# main.net
KiCad netlist of a schematic drawn in EAGLE
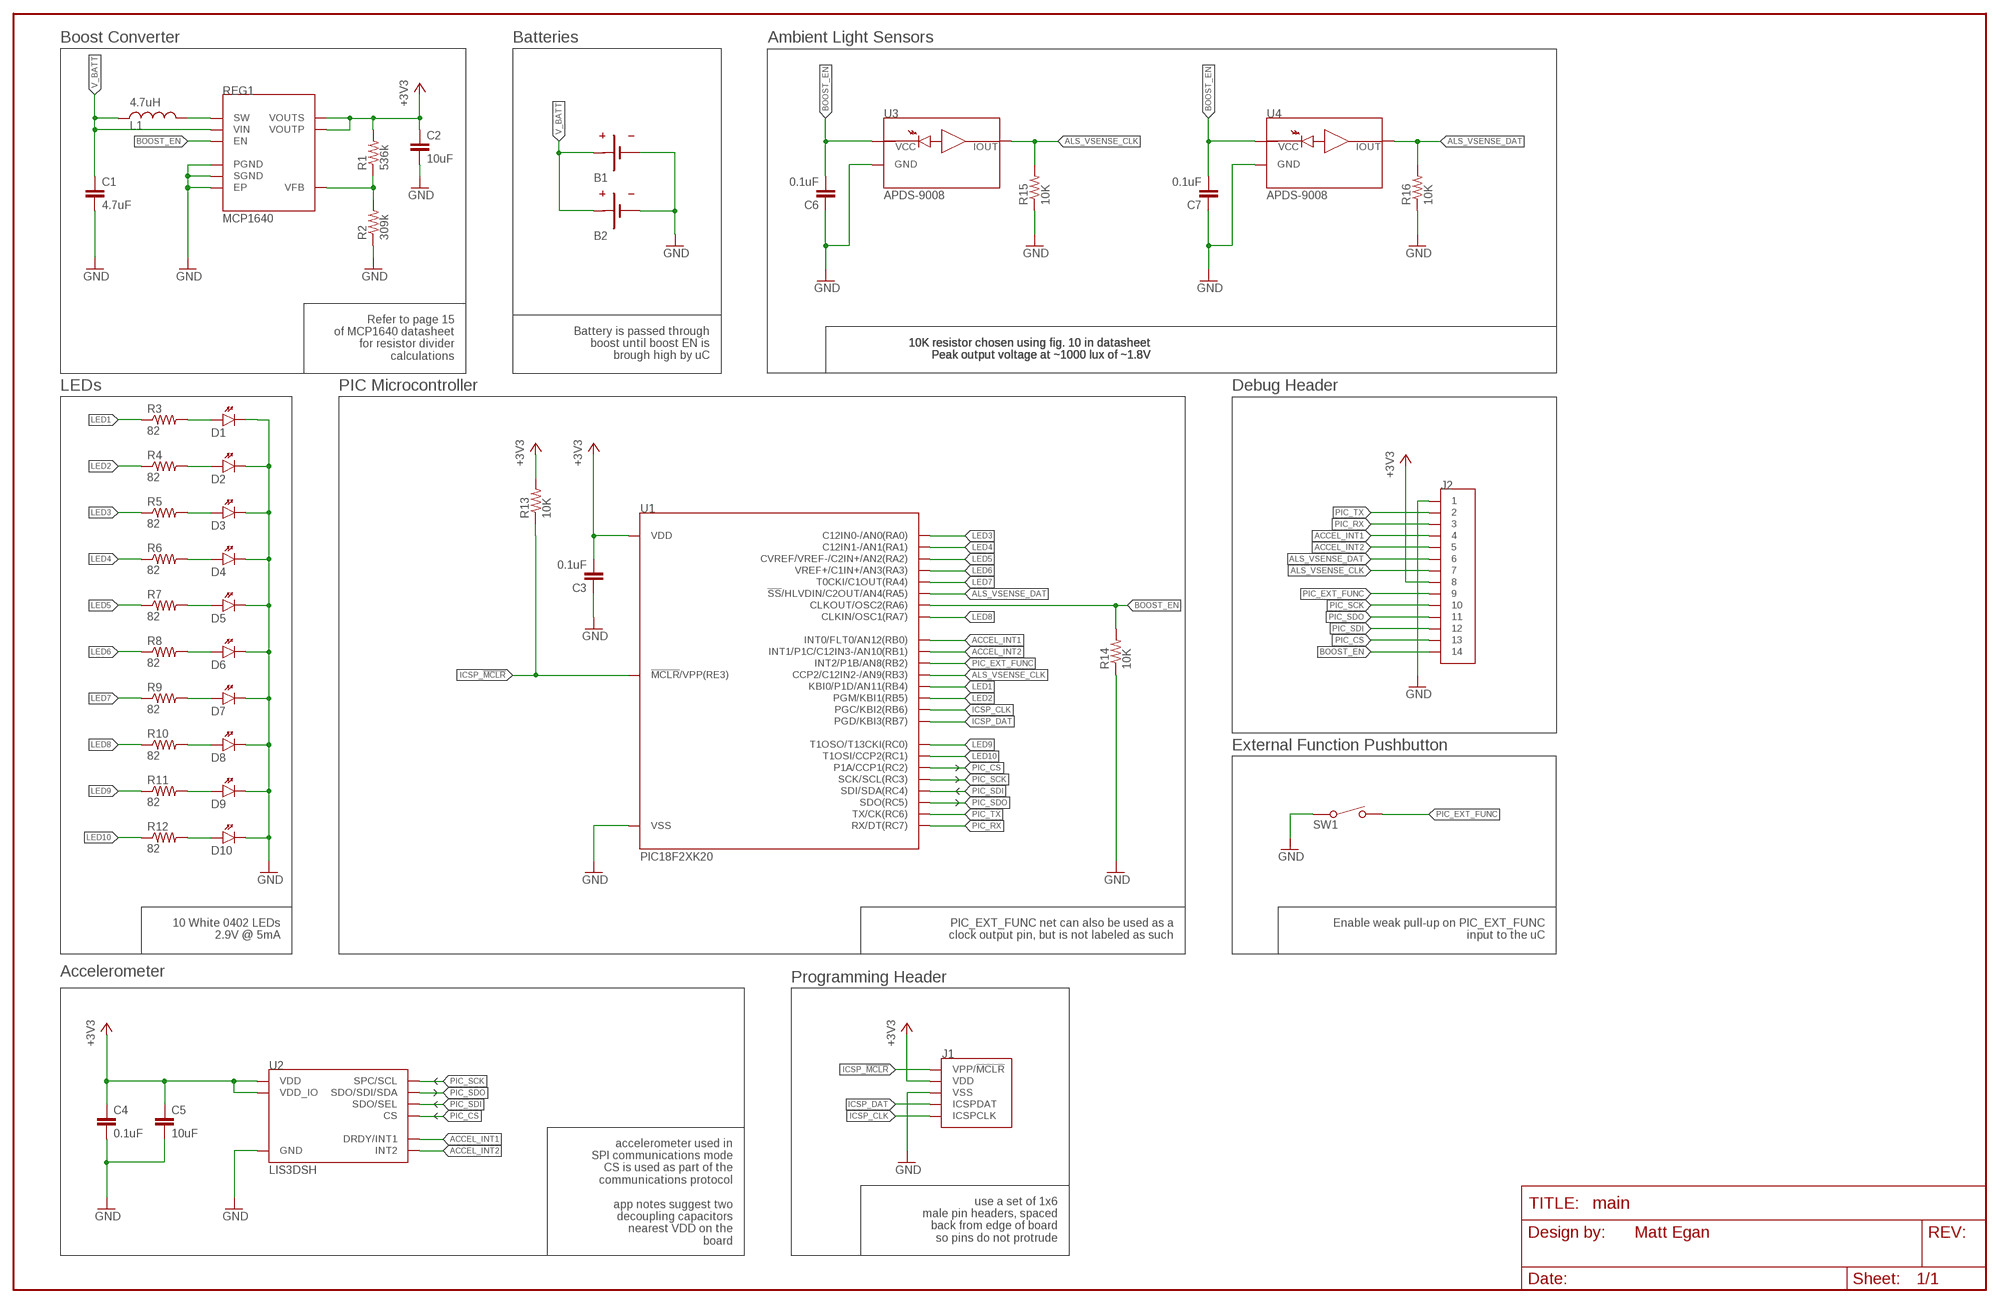
[diagram p0: schematic, sheet 1]

(export (version "E")
  (design (tool "Eeschema 10.0.6"))
  (components
    (comp (ref "B1")
      (value "BATTERYCR-2016/F2N")
      (footprint "eagle-import:CR-2016_F2N")
      (libsource (lib "eagle-import") (part "BATTERYCR-2016/F2N"))
    )
    (comp (ref "B2")
      (value "BATTERYCR-2016/F2N")
      (footprint "eagle-import:CR-2016_F2N")
      (libsource (lib "eagle-import") (part "BATTERYCR-2016/F2N"))
    )
    (comp (ref "C1")
      (value "4.7uF")
      (footprint "eagle-import:SMD-0603")
      (libsource (lib "eagle-import") (part "CAPACITOR0603"))
    )
    (comp (ref "C2")
      (value "10uF")
      (footprint "eagle-import:SMD-0603")
      (libsource (lib "eagle-import") (part "CAPACITOR0603"))
    )
    (comp (ref "C3")
      (value "0.1uF")
      (footprint "eagle-import:SMD-0805")
      (libsource (lib "eagle-import") (part "CAPACITOR0805"))
    )
    (comp (ref "C4")
      (value "0.1uF")
      (footprint "eagle-import:SMD-0805")
      (libsource (lib "eagle-import") (part "CAPACITOR0805"))
    )
    (comp (ref "C5")
      (value "10uF")
      (footprint "eagle-import:SMD-0805")
      (libsource (lib "eagle-import") (part "CAPACITOR0805"))
    )
    (comp (ref "C6")
      (value "0.1uF")
      (footprint "eagle-import:SMD-0805")
      (libsource (lib "eagle-import") (part "CAPACITOR0805"))
    )
    (comp (ref "C7")
      (value "0.1uF")
      (footprint "eagle-import:SMD-0805")
      (libsource (lib "eagle-import") (part "CAPACITOR0805"))
    )
    (comp (ref "D1")
      (value "LED0603")
      (footprint "eagle-import:SMD-0603-P")
      (libsource (lib "eagle-import") (part "LED0603"))
    )
    (comp (ref "D2")
      (value "LED0603")
      (footprint "eagle-import:SMD-0603-P")
      (libsource (lib "eagle-import") (part "LED0603"))
    )
    (comp (ref "D3")
      (value "LED0603")
      (footprint "eagle-import:SMD-0603-P")
      (libsource (lib "eagle-import") (part "LED0603"))
    )
    (comp (ref "D4")
      (value "LED0603")
      (footprint "eagle-import:SMD-0603-P")
      (libsource (lib "eagle-import") (part "LED0603"))
    )
    (comp (ref "D5")
      (value "LED0603")
      (footprint "eagle-import:SMD-0603-P")
      (libsource (lib "eagle-import") (part "LED0603"))
    )
    (comp (ref "D6")
      (value "LED0603")
      (footprint "eagle-import:SMD-0603-P")
      (libsource (lib "eagle-import") (part "LED0603"))
    )
    (comp (ref "D7")
      (value "LED0603")
      (footprint "eagle-import:SMD-0603-P")
      (libsource (lib "eagle-import") (part "LED0603"))
    )
    (comp (ref "D8")
      (value "LED0603")
      (footprint "eagle-import:SMD-0603-P")
      (libsource (lib "eagle-import") (part "LED0603"))
    )
    (comp (ref "D9")
      (value "LED0603")
      (footprint "eagle-import:SMD-0603-P")
      (libsource (lib "eagle-import") (part "LED0603"))
    )
    (comp (ref "D10")
      (value "LED0603")
      (footprint "eagle-import:SMD-0603-P")
      (libsource (lib "eagle-import") (part "LED0603"))
    )
    (comp (ref "J1")
      (value "ICSP-HEADER1X6-0.1-ICSP-PADS")
      (footprint "eagle-import:1X6-0.1-ICSP-PADS")
      (libsource (lib "eagle-import") (part "ICSP-HEADER1X6-0.1-ICSP-PADS"))
    )
    (comp (ref "J2")
      (value "HEADER-141X14-0.05-PADS")
      (footprint "eagle-import:1X14-0.05-PADS")
      (libsource (lib "eagle-import") (part "HEADER-141X14-0.05-PADS"))
    )
    (comp (ref "L1")
      (value "4.7uH")
      (footprint "eagle-import:VLF403210MT")
      (libsource (lib "eagle-import") (part "INDUCTOR"))
    )
    (comp (ref "R1")
      (value "536k")
      (footprint "eagle-import:SMD-0603")
      (libsource (lib "eagle-import") (part "RESISTOR0603"))
    )
    (comp (ref "R2")
      (value "309k")
      (footprint "eagle-import:SMD-0603")
      (libsource (lib "eagle-import") (part "RESISTOR0603"))
    )
    (comp (ref "R3")
      (value "82")
      (footprint "eagle-import:SMD-0603")
      (libsource (lib "eagle-import") (part "RESISTOR0603"))
    )
    (comp (ref "R4")
      (value "82")
      (footprint "eagle-import:SMD-0603")
      (libsource (lib "eagle-import") (part "RESISTOR0603"))
    )
    (comp (ref "R5")
      (value "82")
      (footprint "eagle-import:SMD-0603")
      (libsource (lib "eagle-import") (part "RESISTOR0603"))
    )
    (comp (ref "R6")
      (value "82")
      (footprint "eagle-import:SMD-0603")
      (libsource (lib "eagle-import") (part "RESISTOR0603"))
    )
    (comp (ref "R7")
      (value "82")
      (footprint "eagle-import:SMD-0603")
      (libsource (lib "eagle-import") (part "RESISTOR0603"))
    )
    (comp (ref "R8")
      (value "82")
      (footprint "eagle-import:SMD-0603")
      (libsource (lib "eagle-import") (part "RESISTOR0603"))
    )
    (comp (ref "R9")
      (value "82")
      (footprint "eagle-import:SMD-0603")
      (libsource (lib "eagle-import") (part "RESISTOR0603"))
    )
    (comp (ref "R10")
      (value "82")
      (footprint "eagle-import:SMD-0603")
      (libsource (lib "eagle-import") (part "RESISTOR0603"))
    )
    (comp (ref "R11")
      (value "82")
      (footprint "eagle-import:SMD-0603")
      (libsource (lib "eagle-import") (part "RESISTOR0603"))
    )
    (comp (ref "R12")
      (value "82")
      (footprint "eagle-import:SMD-0603")
      (libsource (lib "eagle-import") (part "RESISTOR0603"))
    )
    (comp (ref "R13")
      (value "10K")
      (footprint "eagle-import:SMD-0603")
      (libsource (lib "eagle-import") (part "RESISTOR0603"))
    )
    (comp (ref "R14")
      (value "10K")
      (footprint "eagle-import:SMD-0603")
      (libsource (lib "eagle-import") (part "RESISTOR0603"))
    )
    (comp (ref "R15")
      (value "10K")
      (footprint "eagle-import:SMD-0603")
      (libsource (lib "eagle-import") (part "RESISTOR0603"))
    )
    (comp (ref "R16")
      (value "10K")
      (footprint "eagle-import:SMD-0603")
      (libsource (lib "eagle-import") (part "RESISTOR0603"))
    )
    (comp (ref "REG1")
      (value "MCP1640")
      (footprint "eagle-import:DFN-8(2X3)")
      (libsource (lib "eagle-import") (part "MCP1640"))
    )
    (comp (ref "SW1")
      (value "B3U-3000P")
      (footprint "eagle-import:B3U-3000P")
      (libsource (lib "eagle-import") (part "B3U-3000P"))
    )
    (comp (ref "U1")
      (value "PIC18F2XK20")
      (footprint "eagle-import:QFN-28")
      (libsource (lib "eagle-import") (part "PIC18F2XK20"))
    )
    (comp (ref "U2")
      (value "LIS3DSH")
      (footprint "eagle-import:LGA-16")
      (libsource (lib "eagle-import") (part "LIS3DSH"))
    )
    (comp (ref "U3")
      (value "APDS-9008")
      (footprint "eagle-import:AVAGO-CHIPLED6")
      (libsource (lib "eagle-import") (part "APDS-9008"))
    )
    (comp (ref "U4")
      (value "APDS-9008")
      (footprint "eagle-import:AVAGO-CHIPLED6")
      (libsource (lib "eagle-import") (part "APDS-9008"))
    )
  )
  (nets
    (net (code "1") (name "+3V3") (class "Default")
      (node (ref "C2") (pin "1") (pinfunction "1_1") (pintype "passive"))
      (node (ref "C3") (pin "2") (pinfunction "2_2") (pintype "passive"))
      (node (ref "C4") (pin "1") (pinfunction "1_1") (pintype "passive"))
      (node (ref "C5") (pin "1") (pinfunction "1_1") (pintype "passive"))
      (node (ref "J1") (pin "P$2") (pinfunction "VDD_P$2") (pintype "bidirectional"))
      (node (ref "J2") (pin "P$8") (pinfunction "8_P$8") (pintype "bidirectional"))
      (node (ref "R1") (pin "2") (pinfunction "2_2") (pintype "passive"))
      (node (ref "R13") (pin "2") (pinfunction "2_2") (pintype "passive"))
      (node (ref "REG1") (pin "6") (pinfunction "VOUTP_6") (pintype "bidirectional"))
      (node (ref "REG1") (pin "7") (pinfunction "VOUTS_7") (pintype "bidirectional"))
      (node (ref "U1") (pin "P$17") (pinfunction "VDD_P$17") (pintype "bidirectional"))
      (node (ref "U2") (pin "P$1") (pinfunction "VDD_IO_P$1") (pintype "power_in"))
      (node (ref "U2") (pin "P$14") (pinfunction "VDD_P$14") (pintype "power_in"))
      (node (ref "U2") (pin "P$15") (pinfunction "VDD_P$15") (pintype "power_in"))
    )
    (net (code "2") (name "/ICSP_~{MCLR}") (class "Default")
      (node (ref "J1") (pin "P$1") (pinfunction "VPP/~{MCLR}_P$1") (pintype "bidirectional"))
      (node (ref "R13") (pin "1") (pinfunction "1_1") (pintype "passive"))
      (node (ref "U1") (pin "P$26") (pinfunction "~{MCLR}/VPP(RE3)_P$26") (pintype "bidirectional"))
    )
    (net (code "3") (name "ACCEL_INT1") (class "Default")
      (node (ref "J2") (pin "P$4") (pinfunction "4_P$4") (pintype "bidirectional"))
      (node (ref "U1") (pin "P$18") (pinfunction "INT0/FLT0/AN12(RB0)_P$18") (pintype "bidirectional"))
      (node (ref "U2") (pin "P$11") (pinfunction "DRDY/INT1_P$11") (pintype "bidirectional"))
    )
    (net (code "4") (name "ACCEL_INT2") (class "Default")
      (node (ref "J2") (pin "P$5") (pinfunction "5_P$5") (pintype "bidirectional"))
      (node (ref "U1") (pin "P$19") (pinfunction "INT1/P1C/C12IN3-/AN10(RB1)_P$19") (pintype "bidirectional"))
      (node (ref "U2") (pin "P$9") (pinfunction "INT2_P$9") (pintype "bidirectional"))
    )
    (net (code "5") (name "ALS_VSENSE_CLK") (class "Default")
      (node (ref "J2") (pin "P$7") (pinfunction "7_P$7") (pintype "bidirectional"))
      (node (ref "R15") (pin "2") (pinfunction "2_2") (pintype "passive"))
      (node (ref "U1") (pin "P$21") (pinfunction "CCP2/C12IN2-/AN9(RB3)_P$21") (pintype "bidirectional"))
      (node (ref "U3") (pin "P$6") (pinfunction "P$IOUT_P$6") (pintype "bidirectional"))
    )
    (net (code "6") (name "ALS_VSENSE_DAT") (class "Default")
      (node (ref "J2") (pin "P$6") (pinfunction "6_P$6") (pintype "bidirectional"))
      (node (ref "R16") (pin "2") (pinfunction "2_2") (pintype "passive"))
      (node (ref "U1") (pin "P$4") (pinfunction "~{SS}/HLVDIN/C2OUT/AN4(RA5)_P$4") (pintype "bidirectional"))
      (node (ref "U4") (pin "P$6") (pinfunction "P$IOUT_P$6") (pintype "bidirectional"))
    )
    (net (code "7") (name "BOOST_EN") (class "Default")
      (node (ref "C6") (pin "2") (pinfunction "2_2") (pintype "passive"))
      (node (ref "C7") (pin "2") (pinfunction "2_2") (pintype "passive"))
      (node (ref "J2") (pin "P$14") (pinfunction "14_P$14") (pintype "bidirectional"))
      (node (ref "R14") (pin "2") (pinfunction "2_2") (pintype "passive"))
      (node (ref "REG1") (pin "4") (pinfunction "EN_4") (pintype "bidirectional"))
      (node (ref "U1") (pin "P$7") (pinfunction "CLKOUT/OSC2(RA6)_P$7") (pintype "bidirectional"))
      (node (ref "U3") (pin "P$1") (pinfunction "P$VCC_P$1") (pintype "bidirectional"))
      (node (ref "U4") (pin "P$1") (pinfunction "P$VCC_P$1") (pintype "bidirectional"))
    )
    (net (code "8") (name "GND") (class "Default")
      (node (ref "B1") (pin "P$-") (pinfunction "P$-_P$-") (pintype "bidirectional"))
      (node (ref "B2") (pin "P$-") (pinfunction "P$-_P$-") (pintype "bidirectional"))
      (node (ref "C1") (pin "2") (pinfunction "2_2") (pintype "passive"))
      (node (ref "C2") (pin "2") (pinfunction "2_2") (pintype "passive"))
      (node (ref "C3") (pin "1") (pinfunction "1_1") (pintype "passive"))
      (node (ref "C4") (pin "2") (pinfunction "2_2") (pintype "passive"))
      (node (ref "C5") (pin "2") (pinfunction "2_2") (pintype "passive"))
      (node (ref "C6") (pin "1") (pinfunction "1_1") (pintype "passive"))
      (node (ref "C7") (pin "1") (pinfunction "1_1") (pintype "passive"))
      (node (ref "D1") (pin "-") (pinfunction "-_-") (pintype "bidirectional"))
      (node (ref "D10") (pin "-") (pinfunction "-_-") (pintype "bidirectional"))
      (node (ref "D2") (pin "-") (pinfunction "-_-") (pintype "bidirectional"))
      (node (ref "D3") (pin "-") (pinfunction "-_-") (pintype "bidirectional"))
      (node (ref "D4") (pin "-") (pinfunction "-_-") (pintype "bidirectional"))
      (node (ref "D5") (pin "-") (pinfunction "-_-") (pintype "bidirectional"))
      (node (ref "D6") (pin "-") (pinfunction "-_-") (pintype "bidirectional"))
      (node (ref "D7") (pin "-") (pinfunction "-_-") (pintype "bidirectional"))
      (node (ref "D8") (pin "-") (pinfunction "-_-") (pintype "bidirectional"))
      (node (ref "D9") (pin "-") (pinfunction "-_-") (pintype "bidirectional"))
      (node (ref "J1") (pin "P$3") (pinfunction "VSS_P$3") (pintype "bidirectional"))
      (node (ref "J2") (pin "P$1") (pinfunction "1_P$1") (pintype "bidirectional"))
      (node (ref "R14") (pin "1") (pinfunction "1_1") (pintype "passive"))
      (node (ref "R15") (pin "1") (pinfunction "1_1") (pintype "passive"))
      (node (ref "R16") (pin "1") (pinfunction "1_1") (pintype "passive"))
      (node (ref "R2") (pin "1") (pinfunction "1_1") (pintype "passive"))
      (node (ref "REG1") (pin "2") (pinfunction "SGND_2") (pintype "bidirectional"))
      (node (ref "REG1") (pin "3") (pinfunction "PGND_3") (pintype "bidirectional"))
      (node (ref "REG1") (pin "EP") (pinfunction "EP_EP") (pintype "bidirectional"))
      (node (ref "SW1") (pin "SW$1") (pinfunction "1_SW$1") (pintype "bidirectional"))
      (node (ref "U1") (pin "P$16") (pinfunction "VSS_P$16") (pintype "bidirectional"))
      (node (ref "U1") (pin "P$5") (pinfunction "VSS_P$5") (pintype "bidirectional"))
      (node (ref "U2") (pin "P$10") (pinfunction "GND_P$10") (pintype "power_in"))
      (node (ref "U2") (pin "P$12") (pinfunction "GND_P$12") (pintype "power_in"))
      (node (ref "U2") (pin "P$13") (pinfunction "GND_P$13") (pintype "power_in"))
      (node (ref "U2") (pin "P$16") (pinfunction "GND_P$16") (pintype "power_in"))
      (node (ref "U2") (pin "P$5") (pinfunction "GND_P$5") (pintype "power_in"))
      (node (ref "U3") (pin "P$4") (pinfunction "GND_P$4") (pintype "bidirectional"))
      (node (ref "U4") (pin "P$4") (pinfunction "GND_P$4") (pintype "bidirectional"))
    )
    (net (code "9") (name "ICSP_CLK") (class "Default")
      (node (ref "J1") (pin "P$5") (pinfunction "ICSPCLK_P$5") (pintype "bidirectional"))
      (node (ref "U1") (pin "P$24") (pinfunction "PGC/KBI2(RB6)_P$24") (pintype "bidirectional"))
    )
    (net (code "10") (name "ICSP_DAT") (class "Default")
      (node (ref "J1") (pin "P$4") (pinfunction "ICSPDAT_P$4") (pintype "bidirectional"))
      (node (ref "U1") (pin "P$25") (pinfunction "PGD/KBI3(RB7)_P$25") (pintype "bidirectional"))
    )
    (net (code "11") (name "LED1") (class "Default")
      (node (ref "R3") (pin "1") (pinfunction "1_1") (pintype "passive"))
      (node (ref "U1") (pin "P$22") (pinfunction "KBI0/P1D/AN11(RB4)_P$22") (pintype "bidirectional"))
    )
    (net (code "12") (name "LED2") (class "Default")
      (node (ref "R4") (pin "1") (pinfunction "1_1") (pintype "passive"))
      (node (ref "U1") (pin "P$23") (pinfunction "PGM/KBI1(RB5)_P$23") (pintype "bidirectional"))
    )
    (net (code "13") (name "LED3") (class "Default")
      (node (ref "R5") (pin "1") (pinfunction "1_1") (pintype "passive"))
      (node (ref "U1") (pin "P$27") (pinfunction "C12IN0-/AN0(RA0)_P$27") (pintype "bidirectional"))
    )
    (net (code "14") (name "LED4") (class "Default")
      (node (ref "R6") (pin "1") (pinfunction "1_1") (pintype "passive"))
      (node (ref "U1") (pin "P$28") (pinfunction "C12IN1-/AN1(RA1)_P$28") (pintype "bidirectional"))
    )
    (net (code "15") (name "LED5") (class "Default")
      (node (ref "R7") (pin "1") (pinfunction "1_1") (pintype "passive"))
      (node (ref "U1") (pin "P$1") (pinfunction "CVREF/VREF-/C2IN+/AN2(RA2)_P$1") (pintype "bidirectional"))
    )
    (net (code "16") (name "LED6") (class "Default")
      (node (ref "R8") (pin "1") (pinfunction "1_1") (pintype "passive"))
      (node (ref "U1") (pin "P$2") (pinfunction "VREF+/C1IN+/AN3(RA3)_P$2") (pintype "bidirectional"))
    )
    (net (code "17") (name "LED7") (class "Default")
      (node (ref "R9") (pin "1") (pinfunction "1_1") (pintype "passive"))
      (node (ref "U1") (pin "P$3") (pinfunction "T0CKI/C1OUT(RA4)_P$3") (pintype "bidirectional"))
    )
    (net (code "18") (name "LED8") (class "Default")
      (node (ref "R10") (pin "1") (pinfunction "1_1") (pintype "passive"))
      (node (ref "U1") (pin "P$6") (pinfunction "CLKIN/OSC1(RA7)_P$6") (pintype "bidirectional"))
    )
    (net (code "19") (name "LED9") (class "Default")
      (node (ref "R11") (pin "1") (pinfunction "1_1") (pintype "passive"))
      (node (ref "U1") (pin "P$8") (pinfunction "T1OSO/T13CKI(RC0)_P$8") (pintype "bidirectional"))
    )
    (net (code "20") (name "LED10") (class "Default")
      (node (ref "R12") (pin "1") (pinfunction "1_1") (pintype "passive"))
      (node (ref "U1") (pin "P$9") (pinfunction "T1OSI/CCP2(RC1)_P$9") (pintype "bidirectional"))
    )
    (net (code "21") (name "Net-(D1-Pad+)") (class "Default")
      (node (ref "D1") (pin "+") (pinfunction "+_+") (pintype "input"))
      (node (ref "R3") (pin "2") (pinfunction "2_2") (pintype "passive"))
    )
    (net (code "22") (name "Net-(D2-Pad+)") (class "Default")
      (node (ref "D2") (pin "+") (pinfunction "+_+") (pintype "input"))
      (node (ref "R4") (pin "2") (pinfunction "2_2") (pintype "passive"))
    )
    (net (code "23") (name "Net-(D3-Pad+)") (class "Default")
      (node (ref "D3") (pin "+") (pinfunction "+_+") (pintype "input"))
      (node (ref "R5") (pin "2") (pinfunction "2_2") (pintype "passive"))
    )
    (net (code "24") (name "Net-(D4-Pad+)") (class "Default")
      (node (ref "D4") (pin "+") (pinfunction "+_+") (pintype "input"))
      (node (ref "R6") (pin "2") (pinfunction "2_2") (pintype "passive"))
    )
    (net (code "25") (name "Net-(D5-Pad+)") (class "Default")
      (node (ref "D5") (pin "+") (pinfunction "+_+") (pintype "input"))
      (node (ref "R7") (pin "2") (pinfunction "2_2") (pintype "passive"))
    )
    (net (code "26") (name "Net-(D6-Pad+)") (class "Default")
      (node (ref "D6") (pin "+") (pinfunction "+_+") (pintype "input"))
      (node (ref "R8") (pin "2") (pinfunction "2_2") (pintype "passive"))
    )
    (net (code "27") (name "Net-(D7-Pad+)") (class "Default")
      (node (ref "D7") (pin "+") (pinfunction "+_+") (pintype "input"))
      (node (ref "R9") (pin "2") (pinfunction "2_2") (pintype "passive"))
    )
    (net (code "28") (name "Net-(D8-Pad+)") (class "Default")
      (node (ref "D8") (pin "+") (pinfunction "+_+") (pintype "input"))
      (node (ref "R10") (pin "2") (pinfunction "2_2") (pintype "passive"))
    )
    (net (code "29") (name "Net-(D9-Pad+)") (class "Default")
      (node (ref "D9") (pin "+") (pinfunction "+_+") (pintype "input"))
      (node (ref "R11") (pin "2") (pinfunction "2_2") (pintype "passive"))
    )
    (net (code "30") (name "Net-(D10-Pad+)") (class "Default")
      (node (ref "D10") (pin "+") (pinfunction "+_+") (pintype "input"))
      (node (ref "R12") (pin "2") (pinfunction "2_2") (pintype "passive"))
    )
    (net (code "31") (name "Net-(L1-2)") (class "Default")
      (node (ref "L1") (pin "P$2") (pinfunction "2_P$2") (pintype "passive"))
      (node (ref "REG1") (pin "5") (pinfunction "SW_5") (pintype "bidirectional"))
    )
    (net (code "32") (name "Net-(REG1-VFB)") (class "Default")
      (node (ref "R1") (pin "1") (pinfunction "1_1") (pintype "passive"))
      (node (ref "R2") (pin "2") (pinfunction "2_2") (pintype "passive"))
      (node (ref "REG1") (pin "1") (pinfunction "VFB_1") (pintype "bidirectional"))
    )
    (net (code "33") (name "PIC_CS") (class "Default")
      (node (ref "J2") (pin "P$13") (pinfunction "13_P$13") (pintype "bidirectional"))
      (node (ref "U1") (pin "P$10") (pinfunction "P1A/CCP1(RC2)_P$10") (pintype "bidirectional"))
      (node (ref "U2") (pin "P$8") (pinfunction "CS_P$8") (pintype "bidirectional"))
    )
    (net (code "34") (name "PIC_EXT_FUNC") (class "Default")
      (node (ref "J2") (pin "P$9") (pinfunction "9_P$9") (pintype "bidirectional"))
      (node (ref "SW1") (pin "SW$2") (pinfunction "3_SW$2") (pintype "bidirectional"))
      (node (ref "U1") (pin "P$20") (pinfunction "INT2/P1B/AN8(RB2)_P$20") (pintype "bidirectional"))
    )
    (net (code "35") (name "PIC_RX") (class "Default")
      (node (ref "J2") (pin "P$3") (pinfunction "3_P$3") (pintype "bidirectional"))
      (node (ref "U1") (pin "P$15") (pinfunction "RX/DT(RC7)_P$15") (pintype "bidirectional"))
    )
    (net (code "36") (name "PIC_SCK") (class "Default")
      (node (ref "J2") (pin "P$10") (pinfunction "10_P$10") (pintype "bidirectional"))
      (node (ref "U1") (pin "P$11") (pinfunction "SCK/SCL(RC3)_P$11") (pintype "bidirectional"))
      (node (ref "U2") (pin "P$4") (pinfunction "SPC/SCL_P$4") (pintype "bidirectional"))
    )
    (net (code "37") (name "PIC_SDI") (class "Default")
      (node (ref "J2") (pin "P$12") (pinfunction "12_P$12") (pintype "bidirectional"))
      (node (ref "U1") (pin "P$12") (pinfunction "SDI/SDA(RC4)_P$12") (pintype "bidirectional"))
      (node (ref "U2") (pin "P$7") (pinfunction "SDO/SEL_P$7") (pintype "bidirectional"))
    )
    (net (code "38") (name "PIC_SDO") (class "Default")
      (node (ref "J2") (pin "P$11") (pinfunction "11_P$11") (pintype "bidirectional"))
      (node (ref "U1") (pin "P$13") (pinfunction "SDO(RC5)_P$13") (pintype "bidirectional"))
      (node (ref "U2") (pin "P$6") (pinfunction "SDO/SDI/SDA_P$6") (pintype "bidirectional"))
    )
    (net (code "39") (name "PIC_TX") (class "Default")
      (node (ref "J2") (pin "P$2") (pinfunction "2_P$2") (pintype "bidirectional"))
      (node (ref "U1") (pin "P$14") (pinfunction "TX/CK(RC6)_P$14") (pintype "bidirectional"))
    )
    (net (code "40") (name "V_BATT") (class "Default")
      (node (ref "B1") (pin "P$+") (pinfunction "P$+_P$+") (pintype "bidirectional"))
      (node (ref "B2") (pin "P$+") (pinfunction "P$+_P$+") (pintype "bidirectional"))
      (node (ref "C1") (pin "1") (pinfunction "1_1") (pintype "passive"))
      (node (ref "L1") (pin "P$1") (pinfunction "1_P$1") (pintype "passive"))
      (node (ref "REG1") (pin "8") (pinfunction "VIN_8") (pintype "bidirectional"))
    )
  )
)
